# Main.net
KiCad netlist of a schematic drawn in Altium Designer
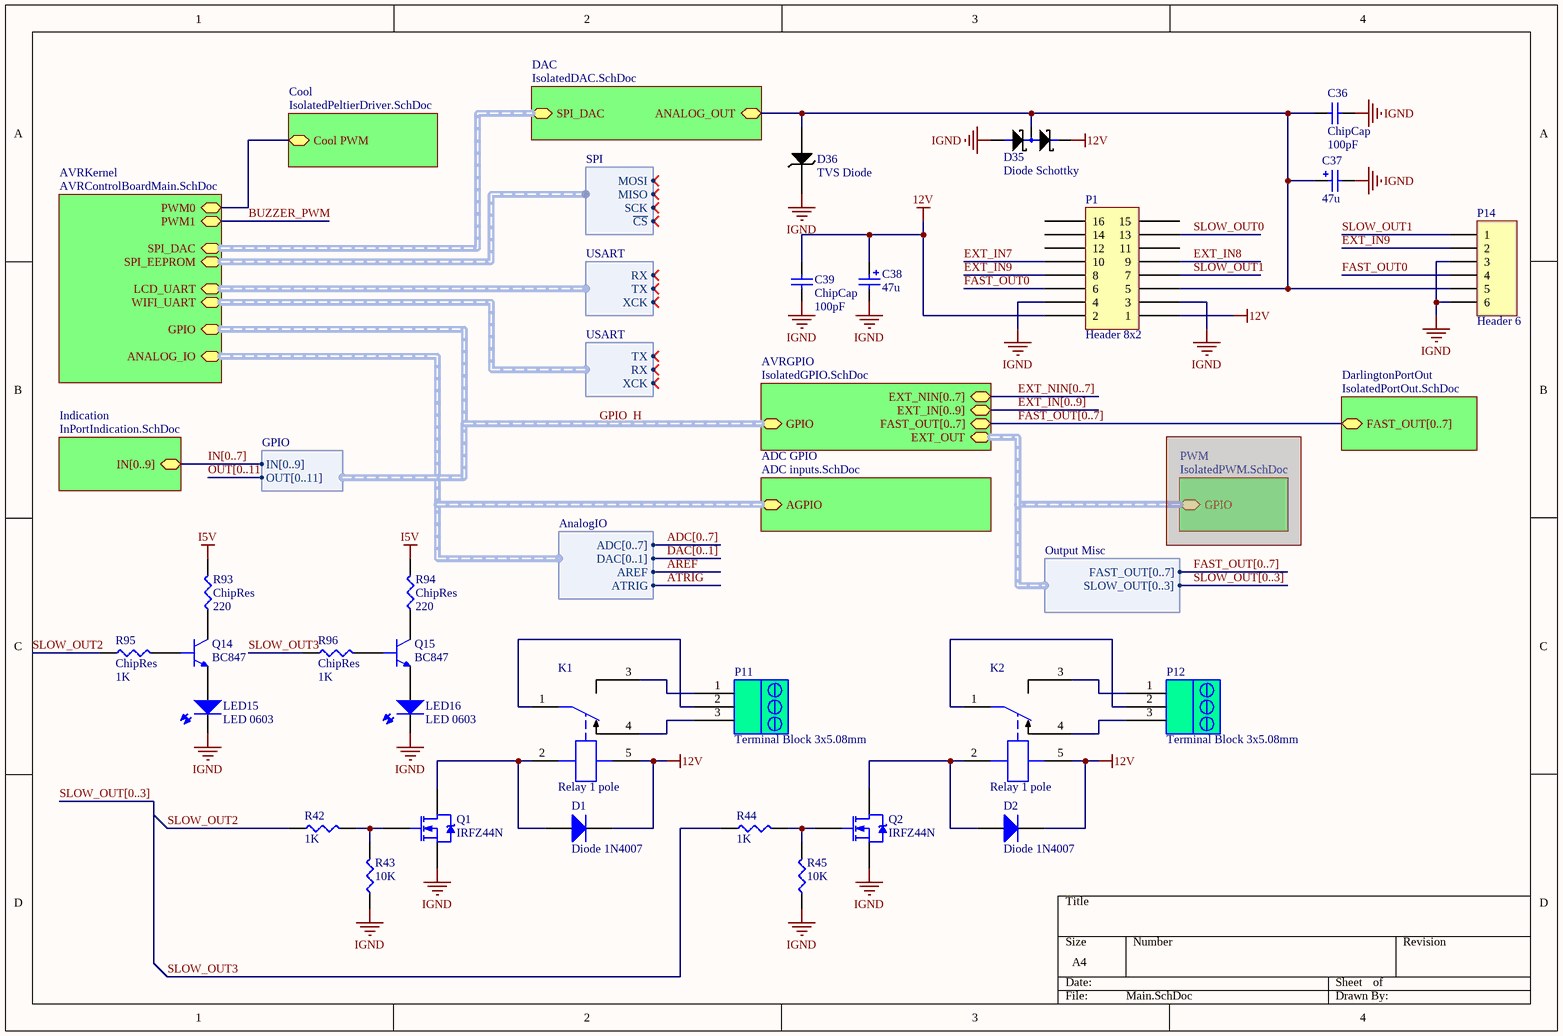
[diagram p0: Main.SchDoc]

(export (version "E")
  (design (tool "Eeschema 10.0.6"))
  (components
    (comp (ref "C36")
      (value "ChipCap")
      (footprint "CAP0805")
      (description "Capacitor")
      (fields (field (name "ALTIUM_VALUE") "100pF") (field (name "PUBLISHER") "Altium Limited"))
      (libsource (lib "Common Devices") (part "ChipCap"))
    )
    (comp (ref "C37")
      (value "47u")
      (footprint "CAPC7343")
      (description "Polarized Capacitor (Radial)")
      (fields (field (name "Comment") "Cap Pol SMD"))
      (libsource (lib "Common Devices") (part "Cap Pol Chip"))
    )
    (comp (ref "C38")
      (value "47u")
      (footprint "CAPC7343")
      (description "Polarized Capacitor (Radial)")
      (fields (field (name "Comment") "Cap Pol SMD"))
      (libsource (lib "Common Devices") (part "Cap Pol Chip"))
    )
    (comp (ref "C39")
      (value "ChipCap")
      (footprint "CAP0805")
      (description "Capacitor")
      (fields (field (name "ALTIUM_VALUE") "100pF") (field (name "PUBLISHER") "Altium Limited"))
      (libsource (lib "Common Devices") (part "ChipCap"))
    )
    (comp (ref "D1")
      (value "Diode 1N4007")
      (footprint "DO-41")
      (description "1 Amp General Purpose Rectifier")
      (fields (field (name "PUBLISHER") "Altium Limited"))
      (libsource (lib "Miscellaneous Devices") (part "Diode 1N4007"))
    )
    (comp (ref "D2")
      (value "Diode 1N4007")
      (footprint "DO-41")
      (description "1 Amp General Purpose Rectifier")
      (fields (field (name "PUBLISHER") "Altium Limited"))
      (libsource (lib "Miscellaneous Devices") (part "Diode 1N4007"))
    )
    (comp (ref "D35")
      (value "Diode Schottky")
      (footprint "SOT23")
      (description "2-Diode Schottky")
      (libsource (lib "Protection") (part "Schottky Diode"))
    )
    (comp (ref "D36")
      (value "TVS Diode")
      (footprint "DO-214AS")
      (libsource (lib "Protection") (part "TVS Diode SMA"))
    )
    (comp (ref "K1")
      (value "Relay 1 pole")
      (footprint "G5LA")
      (description "Relay G5LE 10A Single Pole")
      (libsource (lib "Relays") (part "Relay G5LE"))
    )
    (comp (ref "K2")
      (value "Relay 1 pole")
      (footprint "G5LA")
      (description "Relay G5LE 10A Single Pole")
      (libsource (lib "Relays") (part "Relay G5LE"))
    )
    (comp (ref "LED15") (value "LED 0603") (footprint "LED 0603") (libsource (lib "LEDs") (part "LED0603")))
    (comp (ref "LED16") (value "LED 0603") (footprint "LED 0603") (libsource (lib "LEDs") (part "LED0603")))
    (comp (ref "P1")
      (value "Header 8x2")
      (footprint "Header 8x2 HL")
      (description "Header 16pins (8x2) Hold Latch")
      (libsource (lib "IndustrialConnectors") (part "Header 16pins (8x2)"))
    )
    (comp (ref "P11")
      (value "Terminal Block 3x5.08mm")
      (footprint "Socket 3x5.08")
      (description "Terminal Block Socket Right Angle 3x5.08mm 2-Wall")
      (libsource (lib "IndustrialConnectors") (part "Socket_3x5.08_RA_2Wall"))
    )
    (comp (ref "P12")
      (value "Terminal Block 3x5.08mm")
      (footprint "Socket 3x5.08")
      (description "Terminal Block Socket Right Angle 3x5.08mm 2-Wall")
      (libsource (lib "IndustrialConnectors") (part "Socket_3x5.08_RA_2Wall"))
    )
    (comp (ref "P14")
      (value "Header 6")
      (footprint "HDR1X6")
      (description "Header, 6-Pin")
      (fields (field (name "PUBLISHER") "Altium Limited"))
      (libsource (lib "Miscellaneous Connectors") (part "Header 6"))
    )
    (comp (ref "Q1")
      (value "IRFZ44N")
      (footprint "TO-220AB")
      (description "HEXFET Power MOSFET")
      (fields (field (name "PUBLISHER") "Altium Limited"))
      (libsource (lib "IR Discrete MOSFET - Power") (part "IRFZ44N"))
    )
    (comp (ref "Q2")
      (value "IRFZ44N")
      (footprint "TO-220AB")
      (description "HEXFET Power MOSFET")
      (fields (field (name "PUBLISHER") "Altium Limited"))
      (libsource (lib "IR Discrete MOSFET - Power") (part "IRFZ44N"))
    )
    (comp (ref "Q14")
      (value "BC847")
      (footprint "SOT23")
      (description "NPN transistor")
      (libsource (lib "BJT") (part "BC847"))
    )
    (comp (ref "Q15")
      (value "BC847")
      (footprint "SOT23")
      (description "NPN transistor")
      (libsource (lib "BJT") (part "BC847"))
    )
    (comp (ref "R42")
      (value "1K")
      (footprint "RES0805")
      (description "Chip resistor")
      (fields (field (name "Comment") "ChipRes"))
      (libsource (lib "Common Devices") (part "ChipRes"))
    )
    (comp (ref "R43")
      (value "10K")
      (footprint "RES0805")
      (description "Chip resistor")
      (fields (field (name "Comment") "ChipRes"))
      (libsource (lib "Common Devices") (part "ChipRes"))
    )
    (comp (ref "R44")
      (value "1K")
      (footprint "RES0805")
      (description "Chip resistor")
      (fields (field (name "Comment") "ChipRes"))
      (libsource (lib "Common Devices") (part "ChipRes"))
    )
    (comp (ref "R45")
      (value "10K")
      (footprint "RES0805")
      (description "Chip resistor")
      (fields (field (name "Comment") "ChipRes"))
      (libsource (lib "Common Devices") (part "ChipRes"))
    )
    (comp (ref "R93")
      (value "ChipRes")
      (footprint "RES0805")
      (description "Chip resistor")
      (fields (field (name "ALTIUM_VALUE") "220"))
      (libsource (lib "Common Devices") (part "ChipRes"))
    )
    (comp (ref "R94")
      (value "ChipRes")
      (footprint "RES0805")
      (description "Chip resistor")
      (fields (field (name "ALTIUM_VALUE") "220"))
      (libsource (lib "Common Devices") (part "ChipRes"))
    )
    (comp (ref "R95")
      (value "ChipRes")
      (footprint "RES0805")
      (description "Chip resistor")
      (fields (field (name "ALTIUM_VALUE") "1K"))
      (libsource (lib "Common Devices") (part "ChipRes"))
    )
    (comp (ref "R96")
      (value "ChipRes")
      (footprint "RES0805")
      (description "Chip resistor")
      (fields (field (name "ALTIUM_VALUE") "1K"))
      (libsource (lib "Common Devices") (part "ChipRes"))
    )
  )
  (nets
    (net (code "60") (name "/ANALOG_OUT") (class "Default")
      (node (ref "C36") (pin "1") (pinfunction "1_1") (pintype "passive"))
      (node (ref "C37") (pin "1") (pinfunction "1_1") (pintype "passive"))
      (node (ref "D35") (pin "3") (pinfunction "3_3") (pintype "passive"))
      (node (ref "D36") (pin "2") (pinfunction "2_2") (pintype "passive"))
      (node (ref "P1") (pin "5") (pinfunction "5_5") (pintype "passive"))
      (node (ref "P14") (pin "5") (pinfunction "5_5") (pintype "passive"))
    )
    (net (code "66") (name "/EXT_IN7") (class "Default")
      (node (ref "P1") (pin "10") (pinfunction "10_10") (pintype "passive"))
    )
    (net (code "67") (name "/EXT_IN8") (class "Default")
      (node (ref "P1") (pin "9") (pinfunction "9_9") (pintype "passive"))
    )
    (net (code "68") (name "/EXT_IN9") (class "Default")
      (node (ref "P1") (pin "8") (pinfunction "8_8") (pintype "passive"))
      (node (ref "P14") (pin "2") (pinfunction "2_2") (pintype "passive"))
    )
    (net (code "72") (name "/FAST_OUT0") (class "Default")
      (node (ref "P1") (pin "6") (pinfunction "6_6") (pintype "passive"))
      (node (ref "P14") (pin "4") (pinfunction "4_4") (pintype "passive"))
    )
    (net (code "78") (name "/SLOW_OUT0") (class "Default")
      (node (ref "P1") (pin "13") (pinfunction "13_13") (pintype "passive"))
    )
    (net (code "79") (name "/SLOW_OUT1") (class "Default")
      (node (ref "P1") (pin "7") (pinfunction "7_7") (pintype "passive"))
      (node (ref "P14") (pin "1") (pinfunction "1_1") (pintype "passive"))
    )
    (net (code "80") (name "/SLOW_OUT2") (class "Default")
      (node (ref "R42") (pin "1") (pintype "passive"))
      (node (ref "R95") (pin "1") (pintype "passive"))
    )
    (net (code "81") (name "/SLOW_OUT3") (class "Default")
      (node (ref "R44") (pin "1") (pintype "passive"))
      (node (ref "R96") (pin "1") (pintype "passive"))
    )
    (net (code "88") (name "12V") (class "Default")
      (node (ref "C38") (pin "1") (pinfunction "1_1") (pintype "passive"))
      (node (ref "C39") (pin "1") (pinfunction "1_1") (pintype "passive"))
      (node (ref "D1") (pin "2") (pinfunction "K_2") (pintype "passive"))
      (node (ref "D2") (pin "2") (pinfunction "K_2") (pintype "passive"))
      (node (ref "D35") (pin "2") (pinfunction "2_2") (pintype "passive"))
      (node (ref "K1") (pin "5") (pinfunction "5_5") (pintype "passive"))
      (node (ref "K2") (pin "5") (pinfunction "5_5") (pintype "passive"))
      (node (ref "P1") (pin "1") (pinfunction "1_1") (pintype "passive"))
      (node (ref "P1") (pin "2") (pinfunction "2_2") (pintype "passive"))
    )
    (net (code "89") (name "I5V") (class "Default")
      (node (ref "R93") (pin "2") (pintype "passive"))
      (node (ref "R94") (pin "2") (pintype "passive"))
    )
    (net (code "90") (name "IGND") (class "Default")
      (node (ref "C36") (pin "2") (pinfunction "2_2") (pintype "passive"))
      (node (ref "C37") (pin "2") (pinfunction "2_2") (pintype "passive"))
      (node (ref "C38") (pin "2") (pinfunction "2_2") (pintype "passive"))
      (node (ref "C39") (pin "2") (pinfunction "2_2") (pintype "passive"))
      (node (ref "D35") (pin "1") (pinfunction "1_1") (pintype "passive"))
      (node (ref "D36") (pin "1") (pinfunction "1_1") (pintype "passive"))
      (node (ref "LED15") (pin "1") (pinfunction "1_1") (pintype "passive"))
      (node (ref "LED16") (pin "1") (pinfunction "1_1") (pintype "passive"))
      (node (ref "P1") (pin "3") (pinfunction "3_3") (pintype "passive"))
      (node (ref "P1") (pin "4") (pinfunction "4_4") (pintype "passive"))
      (node (ref "P14") (pin "3") (pinfunction "3_3") (pintype "passive"))
      (node (ref "P14") (pin "6") (pinfunction "6_6") (pintype "passive"))
      (node (ref "Q1") (pin "3") (pinfunction "S_3") (pintype "passive"))
      (node (ref "Q2") (pin "3") (pinfunction "S_3") (pintype "passive"))
      (node (ref "R43") (pin "1") (pintype "passive"))
      (node (ref "R45") (pin "1") (pintype "passive"))
    )
    (net (code "91") (name "Net-(D1-A)") (class "Default")
      (node (ref "D1") (pin "1") (pinfunction "A_1") (pintype "passive"))
      (node (ref "K1") (pin "2") (pinfunction "2_2") (pintype "passive"))
      (node (ref "Q1") (pin "2") (pinfunction "D_2") (pintype "passive"))
    )
    (net (code "92") (name "Net-(D2-A)") (class "Default")
      (node (ref "D2") (pin "1") (pinfunction "A_1") (pintype "passive"))
      (node (ref "K2") (pin "2") (pinfunction "2_2") (pintype "passive"))
      (node (ref "Q2") (pin "2") (pinfunction "D_2") (pintype "passive"))
    )
    (net (code "93") (name "Net-(K1-Pad1)") (class "Default")
      (node (ref "K1") (pin "1") (pinfunction "1_1") (pintype "passive"))
      (node (ref "P11") (pin "2") (pintype "passive"))
    )
    (net (code "94") (name "Net-(K1-Pad3)") (class "Default")
      (node (ref "K1") (pin "3") (pinfunction "3_3") (pintype "passive"))
      (node (ref "P11") (pin "1") (pintype "passive"))
    )
    (net (code "95") (name "Net-(K1-Pad4)") (class "Default")
      (node (ref "K1") (pin "4") (pinfunction "4_4") (pintype "passive"))
      (node (ref "P11") (pin "3") (pintype "passive"))
    )
    (net (code "96") (name "Net-(K2-Pad1)") (class "Default")
      (node (ref "K2") (pin "1") (pinfunction "1_1") (pintype "passive"))
      (node (ref "P12") (pin "2") (pintype "passive"))
    )
    (net (code "97") (name "Net-(K2-Pad3)") (class "Default")
      (node (ref "K2") (pin "3") (pinfunction "3_3") (pintype "passive"))
      (node (ref "P12") (pin "1") (pintype "passive"))
    )
    (net (code "98") (name "Net-(K2-Pad4)") (class "Default")
      (node (ref "K2") (pin "4") (pinfunction "4_4") (pintype "passive"))
      (node (ref "P12") (pin "3") (pintype "passive"))
    )
    (net (code "99") (name "Net-(LED15-Pad2)") (class "Default")
      (node (ref "LED15") (pin "2") (pinfunction "2_2") (pintype "passive"))
      (node (ref "Q14") (pin "2") (pinfunction "2_2") (pintype "passive"))
    )
    (net (code "100") (name "Net-(LED16-Pad2)") (class "Default")
      (node (ref "LED16") (pin "2") (pinfunction "2_2") (pintype "passive"))
      (node (ref "Q15") (pin "2") (pinfunction "2_2") (pintype "passive"))
    )
    (net (code "101") (name "Net-(Q1-G)") (class "Default")
      (node (ref "Q1") (pin "1") (pinfunction "G_1") (pintype "passive"))
      (node (ref "R42") (pin "2") (pintype "passive"))
      (node (ref "R43") (pin "2") (pintype "passive"))
    )
    (net (code "102") (name "Net-(Q2-G)") (class "Default")
      (node (ref "Q2") (pin "1") (pinfunction "G_1") (pintype "passive"))
      (node (ref "R44") (pin "2") (pintype "passive"))
      (node (ref "R45") (pin "2") (pintype "passive"))
    )
    (net (code "103") (name "Net-(Q14-Pad1)") (class "Default")
      (node (ref "Q14") (pin "1") (pinfunction "1_1") (pintype "passive"))
      (node (ref "R95") (pin "2") (pintype "passive"))
    )
    (net (code "104") (name "Net-(Q14-Pad3)") (class "Default")
      (node (ref "Q14") (pin "3") (pinfunction "3_3") (pintype "passive"))
      (node (ref "R93") (pin "1") (pintype "passive"))
    )
    (net (code "105") (name "Net-(Q15-Pad1)") (class "Default")
      (node (ref "Q15") (pin "1") (pinfunction "1_1") (pintype "passive"))
      (node (ref "R96") (pin "2") (pintype "passive"))
    )
    (net (code "106") (name "Net-(Q15-Pad3)") (class "Default")
      (node (ref "Q15") (pin "3") (pinfunction "3_3") (pintype "passive"))
      (node (ref "R94") (pin "1") (pintype "passive"))
    )
    (net (code "107") (name "unconnected-(P1-Pad11)") (class "Default")
      (node (ref "P1") (pin "11") (pinfunction "11_11") (pintype "passive"))
    )
    (net (code "108") (name "unconnected-(P1-Pad12)") (class "Default")
      (node (ref "P1") (pin "12") (pinfunction "12_12") (pintype "passive"))
    )
    (net (code "109") (name "unconnected-(P1-Pad14)") (class "Default")
      (node (ref "P1") (pin "14") (pinfunction "14_14") (pintype "passive"))
    )
    (net (code "110") (name "unconnected-(P1-Pad15)") (class "Default")
      (node (ref "P1") (pin "15") (pinfunction "15_15") (pintype "passive"))
    )
    (net (code "111") (name "unconnected-(P1-Pad16)") (class "Default")
      (node (ref "P1") (pin "16") (pinfunction "16_16") (pintype "passive"))
    )
  )
)
